# ProbadorDeCables_Conexiones_B.net
KiCad netlist of a schematic drawn in Altium Designer
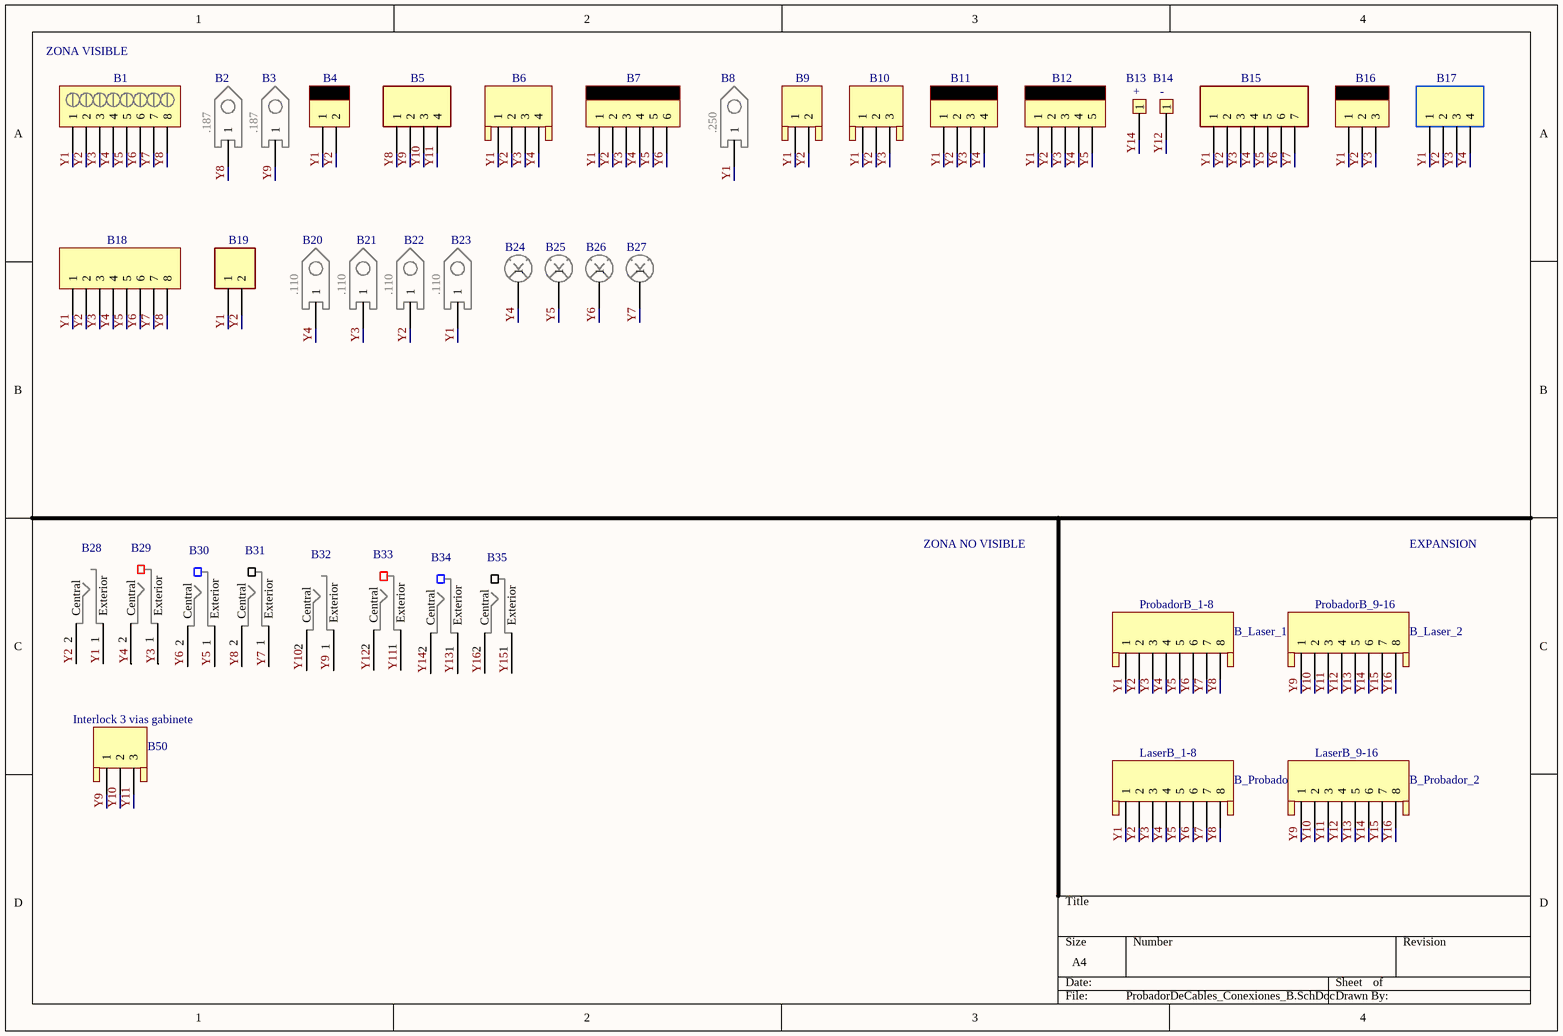
[diagram p0: ProbadorDeCables_Conexiones_B.SchDoc]

(export (version "E")
  (design (tool "Eeschema 10.0.6"))
  (components
    (comp (ref "B1")
      (value "Bornera con tornillos 8 vías")
      (footprint "Bornera con tornillos 8 vías")
      (description "TERMINAL BLOCK SCREW TYPE 5.08")
      (libsource (lib "Nahuel_Connectors_BODY") (part "Bornera con tornillos 8 vías"))
    )
    (comp (ref "B2")
      (value "Pala macho 4.8 para placa")
      (footprint "Nahuel_Connectors_BODY:Pala macho 4.8 para placa")
      (description "CONN QC TAB 0.187 SOLDER")
      (libsource (lib "Nahuel_Connectors_BODY") (part "Pala macho 4.8 para placa"))
    )
    (comp (ref "B3")
      (value "Pala macho 4.8 para placa")
      (footprint "Nahuel_Connectors_BODY:Pala macho 4.8 para placa")
      (description "CONN QC TAB 0.187 SOLDER")
      (libsource (lib "Nahuel_Connectors_BODY") (part "Pala macho 4.8 para placa"))
    )
    (comp (ref "B4")
      (value "Para_SL-156__640445-2")
      (footprint "640445-2")
      (description "CONN HEADER VERT 2POS .156 TIN")
      (libsource (lib "Nahuel_Connectors_BODY") (part "Para_SL-156__640445-2"))
    )
    (comp (ref "B5")
      (value "JST_2.5_4")
      (footprint "B4B-XH-A")
      (description "CONN HEADER XH TOP 4POS 2.5MM")
      (fields (field (name "PUBLISHER") "Altium Limited"))
      (libsource (lib "Nahuel_Connectors_BODY") (part "JST_2.5_4"))
    )
    (comp (ref "B6")
      (value "Para_CST_100__640456-4")
      (footprint "640456-4")
      (description "CONN HEADER VERT 4POS .100 TIN")
      (fields (field (name "PUBLISHER") "Altium Limited"))
      (libsource (lib "Nahuel_Connectors_BODY") (part "Para_CST_100__640456-4"))
    )
    (comp (ref "B7")
      (value "Para_SL-156__640445-6")
      (footprint "640445-6")
      (description "CONN HEADER VERT 6POS .156 TIN")
      (libsource (lib "Nahuel_Connectors_BODY") (part "Para_SL-156__640445-6"))
    )
    (comp (ref "B8")
      (value "Pala macho 6.3 para placa")
      (footprint "Nahuel_Connectors_BODY:Pala macho 6.3 para placa")
      (description "CONN QC TAB 0.250 SOLDER")
      (libsource (lib "Nahuel_Connectors_BODY") (part "Pala macho 6.3 para placa"))
    )
    (comp (ref "B9")
      (value "Para_CST_100__640456-2")
      (footprint "640456-2")
      (description "CONN HEADER VERT 2POS .100 TIN")
      (fields (field (name "PUBLISHER") "Altium Limited"))
      (libsource (lib "Nahuel_Connectors_BODY") (part "Para_CST_100__640456-2"))
    )
    (comp (ref "B10")
      (value "Para_CST_100__640456-3")
      (footprint "640456-3")
      (description "CONN HEADER VERT 3POS .100 TIN")
      (fields (field (name "PUBLISHER") "Altium Limited"))
      (libsource (lib "Nahuel_Connectors_BODY") (part "Para_CST_100__640456-3"))
    )
    (comp (ref "B11")
      (value "Para_SL-156__640445-4")
      (footprint "640445-4")
      (description "CONN HEADER VERT 4POS .156 TIN")
      (libsource (lib "Nahuel_Connectors_BODY") (part "Para_SL-156__640445-4"))
    )
    (comp (ref "B12")
      (value "Para_SL-156__640445-5")
      (footprint "640445-5")
      (description "CONN HEADER VERT 5POS .156 TIN")
      (libsource (lib "Nahuel_Connectors_BODY") (part "Para_SL-156__640445-5"))
    )
    (comp (ref "B13")
      (value "+")
      (footprint "Pin macho para crio")
      (description "CONN PC PIN CIRC 0.058DIA TIN")
      (libsource (lib "Nahuel_Connectors_BODY") (part "Pin macho para crio"))
    )
    (comp (ref "B14")
      (value "-")
      (footprint "Pin macho para crio")
      (description "CONN PC PIN CIRC 0.058DIA TIN")
      (libsource (lib "Nahuel_Connectors_BODY") (part "Pin macho para crio"))
    )
    (comp (ref "B15")
      (value "JST_2.5_7")
      (footprint "Nahuel_Connectors_BODY:B7B-XH-A")
      (description "CONN HEADER XH TOP 7POS 2.5MM")
      (fields (field (name "PUBLISHER") "Altium Limited"))
      (libsource (lib "Nahuel_Connectors_BODY") (part "JST_2.5_7"))
    )
    (comp (ref "B16")
      (value "Para_SL-156__640445-3")
      (footprint "640445-3")
      (description "CONN HEADER VERT 3POS .156 TIN")
      (libsource (lib "Nahuel_Connectors_BODY") (part "Para_SL-156__640445-3"))
    )
    (comp (ref "B17")
      (value "USB 2_0 A")
      (footprint "USB2.0_A")
      (description "CONN RCPT USB2.0 TYPEA 4POS VERT")
      (libsource (lib "Nahuel_Connectors_BODY") (part "USB 2_0 A"))
    )
    (comp (ref "B18")
      (value "Fuente MSP-300-15")
      (footprint "DF11-8DP-2DSA(01)")
      (description "CONN HEADER VERT 8POS 2MM")
      (fields (field (name "PUBLISHER") "Altium Limited"))
      (libsource (lib "Nahuel_Connectors_BODY") (part "DF11-8DP-2DSA(01)"))
    )
    (comp (ref "B19")
      (value "JST_2.5_2")
      (footprint "B2B-XH-A")
      (description "CONN HEADER XH TOP 2POS 2.5MM")
      (fields (field (name "PUBLISHER") "Altium Limited"))
      (libsource (lib "Nahuel_Connectors_BODY") (part "JST_2.5_2"))
    )
    (comp (ref "B20")
      (value "Pala macho 2.7 para placa")
      (footprint "Nahuel_Connectors_BODY:Pala macho 2.7 para placa")
      (description "CONN QC TAB 0.110 SOLDER")
      (libsource (lib "Nahuel_Connectors_BODY") (part "Pala macho 2.7 para placa"))
    )
    (comp (ref "B21")
      (value "Pala macho 2.7 para placa")
      (footprint "Nahuel_Connectors_BODY:Pala macho 2.7 para placa")
      (description "CONN QC TAB 0.110 SOLDER")
      (libsource (lib "Nahuel_Connectors_BODY") (part "Pala macho 2.7 para placa"))
    )
    (comp (ref "B22")
      (value "Pala macho 2.7 para placa")
      (footprint "Nahuel_Connectors_BODY:Pala macho 2.7 para placa")
      (description "CONN QC TAB 0.110 SOLDER")
      (libsource (lib "Nahuel_Connectors_BODY") (part "Pala macho 2.7 para placa"))
    )
    (comp (ref "B23")
      (value "Pala macho 2.7 para placa")
      (footprint "Nahuel_Connectors_BODY:Pala macho 2.7 para placa")
      (description "CONN QC TAB 0.110 SOLDER")
      (libsource (lib "Nahuel_Connectors_BODY") (part "Pala macho 2.7 para placa"))
    )
    (comp (ref "B24")
      (value "Tornillo M4 para placa")
      (footprint "SCREW M4 4 PIN PCB")
      (description "TERM SCREW M4 4 PIN PCB")
      (libsource (lib "Nahuel_Connectors_BODY") (part "Tornillo M4 para placa"))
    )
    (comp (ref "B25")
      (value "Tornillo M4 para placa")
      (footprint "SCREW M4 4 PIN PCB")
      (description "TERM SCREW M4 4 PIN PCB")
      (libsource (lib "Nahuel_Connectors_BODY") (part "Tornillo M4 para placa"))
    )
    (comp (ref "B26")
      (value "Tornillo M4 para placa")
      (footprint "SCREW M4 4 PIN PCB")
      (description "TERM SCREW M4 4 PIN PCB")
      (libsource (lib "Nahuel_Connectors_BODY") (part "Tornillo M4 para placa"))
    )
    (comp (ref "B27")
      (value "Tornillo M4 para placa")
      (footprint "SCREW M4 4 PIN PCB")
      (description "TERM SCREW M4 4 PIN PCB")
      (libsource (lib "Nahuel_Connectors_BODY") (part "Tornillo M4 para placa"))
    )
    (comp (ref "B28")
      (value "RCA mono para placa - Blanco")
      (footprint "RCJ-023")
      (description "CONN RCA JACK MONO 3.2MM PCB")
      (libsource (lib "Nahuel_Connectors_BODY") (part "RCA mono para placa - Blanco"))
    )
    (comp (ref "B29")
      (value "RCA mono para placa - Rojo")
      (footprint "RCJ-022")
      (description "CONN RCA JACK MONO 3.2MM PCB")
      (libsource (lib "Nahuel_Connectors_BODY") (part "RCA mono para placa - Rojo"))
    )
    (comp (ref "B30")
      (value "RCA mono para placa - Azul")
      (footprint "RCJ-025")
      (description "CONN RCA JACK MONO 3.2MM PCB")
      (libsource (lib "Nahuel_Connectors_BODY") (part "RCA mono para placa - Azul"))
    )
    (comp (ref "B31")
      (value "RCA mono para placa - Negro")
      (footprint "RCJ-021")
      (description "CONN RCA JACK MONO 3.2MM PCB")
      (libsource (lib "Nahuel_Connectors_BODY") (part "RCA mono para placa - Negro"))
    )
    (comp (ref "B32")
      (value "RCA mono para placa - Blanco")
      (footprint "RCJ-023")
      (description "CONN RCA JACK MONO 3.2MM PCB")
      (libsource (lib "Nahuel_Connectors_BODY") (part "RCA mono para placa - Blanco"))
    )
    (comp (ref "B33")
      (value "RCA mono para placa - Rojo")
      (footprint "RCJ-022")
      (description "CONN RCA JACK MONO 3.2MM PCB")
      (libsource (lib "Nahuel_Connectors_BODY") (part "RCA mono para placa - Rojo"))
    )
    (comp (ref "B34")
      (value "RCA mono para placa - Azul")
      (footprint "RCJ-025")
      (description "CONN RCA JACK MONO 3.2MM PCB")
      (libsource (lib "Nahuel_Connectors_BODY") (part "RCA mono para placa - Azul"))
    )
    (comp (ref "B35")
      (value "RCA mono para placa - Negro")
      (footprint "RCJ-021")
      (description "CONN RCA JACK MONO 3.2MM PCB")
      (libsource (lib "Nahuel_Connectors_BODY") (part "RCA mono para placa - Negro"))
    )
    (comp (ref "B50")
      (value "Interlock 3 vias gabinete")
      (footprint "640456-3")
      (description "CONN HEADER VERT 3POS .100 TIN")
      (fields (field (name "PUBLISHER") "Altium Limited"))
      (libsource (lib "Nahuel_Connectors_BODY") (part "Para_CST_100__640456-3"))
    )
    (comp (ref "B_Laser_1")
      (value "ProbadorB_1-8")
      (footprint "640456-8")
      (description "CONN HEADER VERT 8POS .100 TIN")
      (libsource (lib "Nahuel_Connectors_BODY") (part "Para_CST_100__640456-8"))
    )
    (comp (ref "B_Laser_2")
      (value "ProbadorB_9-16")
      (footprint "640456-8")
      (description "CONN HEADER VERT 8POS .100 TIN")
      (libsource (lib "Nahuel_Connectors_BODY") (part "Para_CST_100__640456-8"))
    )
    (comp (ref "B_Probador_1")
      (value "LaserB_1-8")
      (footprint "640456-8")
      (description "CONN HEADER VERT 8POS .100 TIN")
      (libsource (lib "Nahuel_Connectors_BODY") (part "Para_CST_100__640456-8"))
    )
    (comp (ref "B_Probador_2")
      (value "LaserB_9-16")
      (footprint "640456-8")
      (description "CONN HEADER VERT 8POS .100 TIN")
      (libsource (lib "Nahuel_Connectors_BODY") (part "Para_CST_100__640456-8"))
    )
  )
  (nets
    (net (code "1") (name "/Y1") (class "Default")
      (node (ref "B1") (pin "1") (pinfunction "1_1") (pintype "passive"))
      (node (ref "B10") (pin "1") (pinfunction "1_1") (pintype "passive"))
      (node (ref "B11") (pin "1") (pinfunction "1_1") (pintype "passive"))
      (node (ref "B12") (pin "1") (pinfunction "1_1") (pintype "passive"))
      (node (ref "B15") (pin "1") (pinfunction "1_1") (pintype "passive"))
      (node (ref "B16") (pin "1") (pinfunction "1_1") (pintype "passive"))
      (node (ref "B17") (pin "1") (pinfunction "1_1") (pintype "passive"))
      (node (ref "B18") (pin "1") (pinfunction "1_1") (pintype "passive"))
      (node (ref "B19") (pin "1") (pinfunction "1_1") (pintype "passive"))
      (node (ref "B23") (pin "1") (pinfunction "1_1") (pintype "passive"))
      (node (ref "B28") (pin "1") (pinfunction "Exterior_1") (pintype "passive"))
      (node (ref "B4") (pin "1") (pinfunction "1_1") (pintype "passive"))
      (node (ref "B6") (pin "1") (pinfunction "1_1") (pintype "passive"))
      (node (ref "B7") (pin "1") (pinfunction "1_1") (pintype "passive"))
      (node (ref "B8") (pin "1") (pinfunction "1_1") (pintype "passive"))
      (node (ref "B9") (pin "1") (pinfunction "1_1") (pintype "passive"))
      (node (ref "B_Laser_1") (pin "1") (pinfunction "1_1") (pintype "passive"))
      (node (ref "B_Probador_1") (pin "1") (pinfunction "1_1") (pintype "passive"))
    )
    (net (code "2") (name "/Y2") (class "Default")
      (node (ref "B1") (pin "2") (pinfunction "2_2") (pintype "passive"))
      (node (ref "B10") (pin "2") (pinfunction "2_2") (pintype "passive"))
      (node (ref "B11") (pin "2") (pinfunction "2_2") (pintype "passive"))
      (node (ref "B12") (pin "2") (pinfunction "2_2") (pintype "passive"))
      (node (ref "B15") (pin "2") (pinfunction "2_2") (pintype "passive"))
      (node (ref "B16") (pin "2") (pinfunction "2_2") (pintype "passive"))
      (node (ref "B17") (pin "2") (pinfunction "2_2") (pintype "passive"))
      (node (ref "B18") (pin "2") (pinfunction "2_2") (pintype "passive"))
      (node (ref "B19") (pin "2") (pinfunction "2_2") (pintype "passive"))
      (node (ref "B22") (pin "1") (pinfunction "1_1") (pintype "passive"))
      (node (ref "B28") (pin "2") (pinfunction "Central_2") (pintype "passive"))
      (node (ref "B4") (pin "2") (pinfunction "2_2") (pintype "passive"))
      (node (ref "B6") (pin "2") (pinfunction "2_2") (pintype "passive"))
      (node (ref "B7") (pin "2") (pinfunction "2_2") (pintype "passive"))
      (node (ref "B9") (pin "2") (pinfunction "2_2") (pintype "passive"))
      (node (ref "B_Laser_1") (pin "2") (pinfunction "2_2") (pintype "passive"))
      (node (ref "B_Probador_1") (pin "2") (pinfunction "2_2") (pintype "passive"))
    )
    (net (code "3") (name "/Y3") (class "Default")
      (node (ref "B1") (pin "3") (pinfunction "3_3") (pintype "passive"))
      (node (ref "B10") (pin "3") (pinfunction "3_3") (pintype "passive"))
      (node (ref "B11") (pin "3") (pinfunction "3_3") (pintype "passive"))
      (node (ref "B12") (pin "3") (pinfunction "3_3") (pintype "passive"))
      (node (ref "B15") (pin "3") (pinfunction "3_3") (pintype "passive"))
      (node (ref "B16") (pin "3") (pinfunction "3_3") (pintype "passive"))
      (node (ref "B17") (pin "3") (pinfunction "3_3") (pintype "passive"))
      (node (ref "B18") (pin "3") (pinfunction "3_3") (pintype "passive"))
      (node (ref "B21") (pin "1") (pinfunction "1_1") (pintype "passive"))
      (node (ref "B29") (pin "1") (pinfunction "Exterior_1") (pintype "passive"))
      (node (ref "B6") (pin "3") (pinfunction "3_3") (pintype "passive"))
      (node (ref "B7") (pin "3") (pinfunction "3_3") (pintype "passive"))
      (node (ref "B_Laser_1") (pin "3") (pinfunction "3_3") (pintype "passive"))
      (node (ref "B_Probador_1") (pin "3") (pinfunction "3_3") (pintype "passive"))
    )
    (net (code "4") (name "/Y4") (class "Default")
      (node (ref "B1") (pin "4") (pinfunction "4_4") (pintype "passive"))
      (node (ref "B11") (pin "4") (pinfunction "4_4") (pintype "passive"))
      (node (ref "B12") (pin "4") (pinfunction "4_4") (pintype "passive"))
      (node (ref "B15") (pin "4") (pinfunction "4_4") (pintype "passive"))
      (node (ref "B17") (pin "4") (pinfunction "4_4") (pintype "passive"))
      (node (ref "B18") (pin "4") (pinfunction "4_4") (pintype "passive"))
      (node (ref "B20") (pin "1") (pinfunction "1_1") (pintype "passive"))
      (node (ref "B24") (pin "1") (pinfunction "1_1") (pintype "passive"))
      (node (ref "B29") (pin "2") (pinfunction "Central_2") (pintype "passive"))
      (node (ref "B6") (pin "4") (pinfunction "4_4") (pintype "passive"))
      (node (ref "B7") (pin "4") (pinfunction "4_4") (pintype "passive"))
      (node (ref "B_Laser_1") (pin "4") (pinfunction "4_4") (pintype "passive"))
      (node (ref "B_Probador_1") (pin "4") (pinfunction "4_4") (pintype "passive"))
    )
    (net (code "5") (name "/Y5") (class "Default")
      (node (ref "B1") (pin "5") (pinfunction "5_5") (pintype "passive"))
      (node (ref "B12") (pin "5") (pinfunction "5_5") (pintype "passive"))
      (node (ref "B15") (pin "5") (pinfunction "5_5") (pintype "passive"))
      (node (ref "B18") (pin "5") (pinfunction "5_5") (pintype "passive"))
      (node (ref "B25") (pin "1") (pinfunction "1_1") (pintype "passive"))
      (node (ref "B30") (pin "1") (pinfunction "Exterior_1") (pintype "passive"))
      (node (ref "B7") (pin "5") (pinfunction "5_5") (pintype "passive"))
      (node (ref "B_Laser_1") (pin "5") (pinfunction "5_5") (pintype "passive"))
      (node (ref "B_Probador_1") (pin "5") (pinfunction "5_5") (pintype "passive"))
    )
    (net (code "6") (name "/Y6") (class "Default")
      (node (ref "B1") (pin "6") (pinfunction "6_6") (pintype "passive"))
      (node (ref "B15") (pin "6") (pinfunction "6_6") (pintype "passive"))
      (node (ref "B18") (pin "6") (pinfunction "6_6") (pintype "passive"))
      (node (ref "B26") (pin "1") (pinfunction "1_1") (pintype "passive"))
      (node (ref "B30") (pin "2") (pinfunction "Central_2") (pintype "passive"))
      (node (ref "B7") (pin "6") (pinfunction "6_6") (pintype "passive"))
      (node (ref "B_Laser_1") (pin "6") (pinfunction "6_6") (pintype "passive"))
      (node (ref "B_Probador_1") (pin "6") (pinfunction "6_6") (pintype "passive"))
    )
    (net (code "7") (name "/Y7") (class "Default")
      (node (ref "B1") (pin "7") (pinfunction "7_7") (pintype "passive"))
      (node (ref "B15") (pin "7") (pinfunction "7_7") (pintype "passive"))
      (node (ref "B18") (pin "7") (pinfunction "7_7") (pintype "passive"))
      (node (ref "B27") (pin "1") (pinfunction "1_1") (pintype "passive"))
      (node (ref "B31") (pin "1") (pinfunction "Exterior_1") (pintype "passive"))
      (node (ref "B_Laser_1") (pin "7") (pinfunction "7_7") (pintype "passive"))
      (node (ref "B_Probador_1") (pin "7") (pinfunction "7_7") (pintype "passive"))
    )
    (net (code "8") (name "/Y8") (class "Default")
      (node (ref "B1") (pin "8") (pinfunction "8_8") (pintype "passive"))
      (node (ref "B18") (pin "8") (pinfunction "8_8") (pintype "passive"))
      (node (ref "B2") (pin "1") (pinfunction "1_1") (pintype "passive"))
      (node (ref "B31") (pin "2") (pinfunction "Central_2") (pintype "passive"))
      (node (ref "B5") (pin "1") (pinfunction "1_1") (pintype "passive"))
      (node (ref "B_Laser_1") (pin "8") (pinfunction "8_8") (pintype "passive"))
      (node (ref "B_Probador_1") (pin "8") (pinfunction "8_8") (pintype "passive"))
    )
    (net (code "9") (name "/Y9") (class "Default")
      (node (ref "B3") (pin "1") (pinfunction "1_1") (pintype "passive"))
      (node (ref "B32") (pin "1") (pinfunction "Exterior_1") (pintype "passive"))
      (node (ref "B5") (pin "2") (pinfunction "2_2") (pintype "passive"))
      (node (ref "B50") (pin "1") (pinfunction "1_1") (pintype "passive"))
      (node (ref "B_Laser_2") (pin "1") (pinfunction "1_1") (pintype "passive"))
      (node (ref "B_Probador_2") (pin "1") (pinfunction "1_1") (pintype "passive"))
    )
    (net (code "10") (name "/Y10") (class "Default")
      (node (ref "B32") (pin "2") (pinfunction "Central_2") (pintype "passive"))
      (node (ref "B5") (pin "3") (pinfunction "3_3") (pintype "passive"))
      (node (ref "B50") (pin "2") (pinfunction "2_2") (pintype "passive"))
      (node (ref "B_Laser_2") (pin "2") (pinfunction "2_2") (pintype "passive"))
      (node (ref "B_Probador_2") (pin "2") (pinfunction "2_2") (pintype "passive"))
    )
    (net (code "11") (name "/Y11") (class "Default")
      (node (ref "B33") (pin "1") (pinfunction "Exterior_1") (pintype "passive"))
      (node (ref "B5") (pin "4") (pinfunction "4_4") (pintype "passive"))
      (node (ref "B50") (pin "3") (pinfunction "3_3") (pintype "passive"))
      (node (ref "B_Laser_2") (pin "3") (pinfunction "3_3") (pintype "passive"))
      (node (ref "B_Probador_2") (pin "3") (pinfunction "3_3") (pintype "passive"))
    )
    (net (code "12") (name "/Y12") (class "Default")
      (node (ref "B14") (pin "1") (pinfunction "1_1") (pintype "passive"))
      (node (ref "B33") (pin "2") (pinfunction "Central_2") (pintype "passive"))
      (node (ref "B_Laser_2") (pin "4") (pinfunction "4_4") (pintype "passive"))
      (node (ref "B_Probador_2") (pin "4") (pinfunction "4_4") (pintype "passive"))
    )
    (net (code "13") (name "/Y13") (class "Default")
      (node (ref "B34") (pin "1") (pinfunction "Exterior_1") (pintype "passive"))
      (node (ref "B_Laser_2") (pin "5") (pinfunction "5_5") (pintype "passive"))
      (node (ref "B_Probador_2") (pin "5") (pinfunction "5_5") (pintype "passive"))
    )
    (net (code "14") (name "/Y14") (class "Default")
      (node (ref "B13") (pin "1") (pinfunction "1_1") (pintype "passive"))
      (node (ref "B34") (pin "2") (pinfunction "Central_2") (pintype "passive"))
      (node (ref "B_Laser_2") (pin "6") (pinfunction "6_6") (pintype "passive"))
      (node (ref "B_Probador_2") (pin "6") (pinfunction "6_6") (pintype "passive"))
    )
    (net (code "15") (name "/Y15") (class "Default")
      (node (ref "B35") (pin "1") (pinfunction "Exterior_1") (pintype "passive"))
      (node (ref "B_Laser_2") (pin "7") (pinfunction "7_7") (pintype "passive"))
      (node (ref "B_Probador_2") (pin "7") (pinfunction "7_7") (pintype "passive"))
    )
    (net (code "16") (name "/Y16") (class "Default")
      (node (ref "B35") (pin "2") (pinfunction "Central_2") (pintype "passive"))
      (node (ref "B_Laser_2") (pin "8") (pinfunction "8_8") (pintype "passive"))
      (node (ref "B_Probador_2") (pin "8") (pinfunction "8_8") (pintype "passive"))
    )
  )
)
